# xkid_sensor_0_1.net
KiCad netlist of a schematic drawn in EAGLE
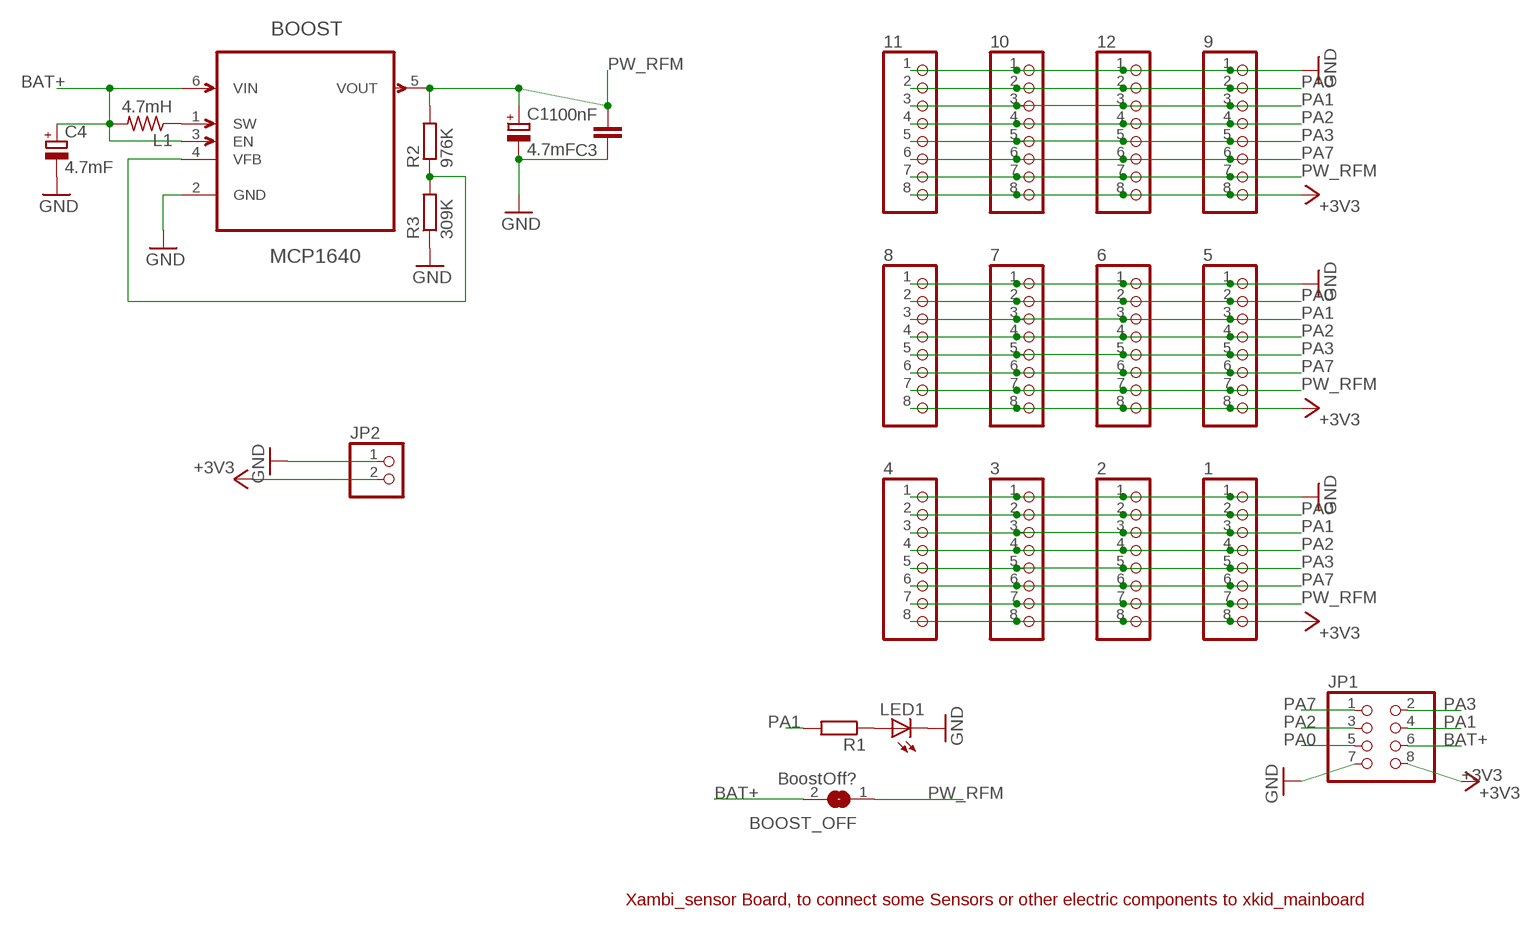
[diagram p0: schematic, sheet 1]

(export (version "E")
  (design (tool "Eeschema 10.0.6"))
  (components
    (comp (ref "1")
      (value "PINHD-1X8_2.00")
      (footprint "eagle-import:1X08M")
      (libsource (lib "eagle-import") (part "PINHD-1X8_2.00"))
    )
    (comp (ref "2")
      (value "PINHD-1X8_2.00")
      (footprint "eagle-import:1X08M")
      (libsource (lib "eagle-import") (part "PINHD-1X8_2.00"))
    )
    (comp (ref "3")
      (value "PINHD-1X8_2.00")
      (footprint "eagle-import:1X08M")
      (libsource (lib "eagle-import") (part "PINHD-1X8_2.00"))
    )
    (comp (ref "4")
      (value "PINHD-1X8_2.00")
      (footprint "eagle-import:1X08M")
      (libsource (lib "eagle-import") (part "PINHD-1X8_2.00"))
    )
    (comp (ref "5")
      (value "PINHD-1X8_2.00")
      (footprint "eagle-import:1X08M")
      (libsource (lib "eagle-import") (part "PINHD-1X8_2.00"))
    )
    (comp (ref "6")
      (value "PINHD-1X8_2.00")
      (footprint "eagle-import:1X08M")
      (libsource (lib "eagle-import") (part "PINHD-1X8_2.00"))
    )
    (comp (ref "7")
      (value "PINHD-1X8_2.00")
      (footprint "eagle-import:1X08M")
      (libsource (lib "eagle-import") (part "PINHD-1X8_2.00"))
    )
    (comp (ref "8")
      (value "PINHD-1X8_2.00")
      (footprint "eagle-import:1X08M")
      (libsource (lib "eagle-import") (part "PINHD-1X8_2.00"))
    )
    (comp (ref "9")
      (value "PINHD-1X8_2.00")
      (footprint "eagle-import:1X08M")
      (libsource (lib "eagle-import") (part "PINHD-1X8_2.00"))
    )
    (comp (ref "10")
      (value "PINHD-1X8_2.00")
      (footprint "eagle-import:1X08M")
      (libsource (lib "eagle-import") (part "PINHD-1X8_2.00"))
    )
    (comp (ref "11")
      (value "PINHD-1X8_2.00")
      (footprint "eagle-import:1X08M")
      (libsource (lib "eagle-import") (part "PINHD-1X8_2.00"))
    )
    (comp (ref "12")
      (value "PINHD-1X8_2.00")
      (footprint "eagle-import:1X08M")
      (libsource (lib "eagle-import") (part "PINHD-1X8_2.00"))
    )
    (comp (ref "BOOST")
      (value "MCP1640")
      (footprint "eagle-import:SOT95P270X145-6N")
      (fields (field (name "MPN") "MCP1640BT-I/CHY"))
      (libsource (lib "eagle-import") (part "MCP1640BT-I/CHY"))
    )
    (comp (ref "BOOST_OFF")
      (value "BoostOff?")
      (footprint "eagle-import:SJ")
      (libsource (lib "eagle-import") (part "SJ"))
    )
    (comp (ref "C1")
      (value "4.7mF")
      (footprint "eagle-import:CT3216")
      (libsource (lib "eagle-import") (part "CPOL-EUCT3216"))
    )
    (comp (ref "C3")
      (value "100nF")
      (footprint "eagle-import:C0805K")
      (libsource (lib "eagle-import") (part "C-EUC0805K"))
    )
    (comp (ref "C4")
      (value "4.7mF")
      (footprint "eagle-import:CT3216")
      (libsource (lib "eagle-import") (part "CPOL-EUCT3216"))
    )
    (comp (ref "JP1")
      (value "PINHD-2X4_2.54")
      (footprint "eagle-import:2X04")
      (libsource (lib "eagle-import") (part "PINHD-2X4_2.54"))
    )
    (comp (ref "JP2")
      (value "PINHD-1X2")
      (footprint "eagle-import:1X02")
      (libsource (lib "eagle-import") (part "PINHD-1X2"))
    )
    (comp (ref "L1")
      (value "4.7mH")
      (footprint "eagle-import:0204_5")
      (libsource (lib "eagle-import") (part "R-US_0204/5"))
    )
    (comp (ref "LED1")
      (value "LEDCHIPLED_0805")
      (footprint "eagle-import:CHIPLED_0805")
      (libsource (lib "eagle-import") (part "LEDCHIPLED_0805"))
    )
    (comp (ref "R1")
      (value "R-EU_R0805")
      (footprint "eagle-import:R0805")
      (libsource (lib "eagle-import") (part "R-EU_R0805"))
    )
    (comp (ref "R2")
      (value "976K")
      (footprint "eagle-import:R0805")
      (libsource (lib "eagle-import") (part "R-EU_R0805"))
    )
    (comp (ref "R3")
      (value "309K")
      (footprint "eagle-import:R0805")
      (libsource (lib "eagle-import") (part "R-EU_R0805"))
    )
  )
  (nets
    (net (code "1") (name "+3V3") (class "Default")
      (node (ref "1") (pin "8") (pinfunction "8_8") (pintype "passive"))
      (node (ref "10") (pin "8") (pinfunction "8_8") (pintype "passive"))
      (node (ref "11") (pin "8") (pinfunction "8_8") (pintype "passive"))
      (node (ref "12") (pin "8") (pinfunction "8_8") (pintype "passive"))
      (node (ref "2") (pin "8") (pinfunction "8_8") (pintype "passive"))
      (node (ref "3") (pin "8") (pinfunction "8_8") (pintype "passive"))
      (node (ref "4") (pin "8") (pinfunction "8_8") (pintype "passive"))
      (node (ref "5") (pin "8") (pinfunction "8_8") (pintype "passive"))
      (node (ref "6") (pin "8") (pinfunction "8_8") (pintype "passive"))
      (node (ref "7") (pin "8") (pinfunction "8_8") (pintype "passive"))
      (node (ref "8") (pin "8") (pinfunction "8_8") (pintype "passive"))
      (node (ref "9") (pin "8") (pinfunction "8_8") (pintype "passive"))
      (node (ref "JP1") (pin "8") (pinfunction "8_8") (pintype "passive"))
      (node (ref "JP2") (pin "2") (pinfunction "2_2") (pintype "passive"))
    )
    (net (code "2") (name "/BAT+") (class "Default")
      (node (ref "BOOST") (pin "3") (pinfunction "EN_3") (pintype "input"))
      (node (ref "BOOST") (pin "6") (pinfunction "VIN_6") (pintype "input"))
      (node (ref "BOOST_OFF") (pin "2") (pinfunction "2_2") (pintype "passive"))
      (node (ref "C4") (pin "+") (pinfunction "+_+") (pintype "passive"))
      (node (ref "JP1") (pin "6") (pinfunction "6_6") (pintype "passive"))
      (node (ref "L1") (pin "2") (pinfunction "2_2") (pintype "passive"))
    )
    (net (code "3") (name "/PA0") (class "Default")
      (node (ref "1") (pin "2") (pinfunction "2_2") (pintype "passive"))
      (node (ref "10") (pin "2") (pinfunction "2_2") (pintype "passive"))
      (node (ref "11") (pin "2") (pinfunction "2_2") (pintype "passive"))
      (node (ref "12") (pin "2") (pinfunction "2_2") (pintype "passive"))
      (node (ref "2") (pin "2") (pinfunction "2_2") (pintype "passive"))
      (node (ref "3") (pin "2") (pinfunction "2_2") (pintype "passive"))
      (node (ref "4") (pin "2") (pinfunction "2_2") (pintype "passive"))
      (node (ref "5") (pin "2") (pinfunction "2_2") (pintype "passive"))
      (node (ref "6") (pin "2") (pinfunction "2_2") (pintype "passive"))
      (node (ref "7") (pin "2") (pinfunction "2_2") (pintype "passive"))
      (node (ref "8") (pin "2") (pinfunction "2_2") (pintype "passive"))
      (node (ref "9") (pin "2") (pinfunction "2_2") (pintype "passive"))
      (node (ref "JP1") (pin "5") (pinfunction "5_5") (pintype "passive"))
    )
    (net (code "4") (name "/PA1") (class "Default")
      (node (ref "1") (pin "3") (pinfunction "3_3") (pintype "passive"))
      (node (ref "10") (pin "3") (pinfunction "3_3") (pintype "passive"))
      (node (ref "11") (pin "3") (pinfunction "3_3") (pintype "passive"))
      (node (ref "12") (pin "3") (pinfunction "3_3") (pintype "passive"))
      (node (ref "2") (pin "3") (pinfunction "3_3") (pintype "passive"))
      (node (ref "3") (pin "3") (pinfunction "3_3") (pintype "passive"))
      (node (ref "4") (pin "3") (pinfunction "3_3") (pintype "passive"))
      (node (ref "5") (pin "3") (pinfunction "3_3") (pintype "passive"))
      (node (ref "6") (pin "3") (pinfunction "3_3") (pintype "passive"))
      (node (ref "7") (pin "3") (pinfunction "3_3") (pintype "passive"))
      (node (ref "8") (pin "3") (pinfunction "3_3") (pintype "passive"))
      (node (ref "9") (pin "3") (pinfunction "3_3") (pintype "passive"))
      (node (ref "JP1") (pin "4") (pinfunction "4_4") (pintype "passive"))
      (node (ref "R1") (pin "2") (pinfunction "2_2") (pintype "passive"))
    )
    (net (code "5") (name "/PA2") (class "Default")
      (node (ref "1") (pin "4") (pinfunction "4_4") (pintype "passive"))
      (node (ref "10") (pin "4") (pinfunction "4_4") (pintype "passive"))
      (node (ref "11") (pin "4") (pinfunction "4_4") (pintype "passive"))
      (node (ref "12") (pin "4") (pinfunction "4_4") (pintype "passive"))
      (node (ref "2") (pin "4") (pinfunction "4_4") (pintype "passive"))
      (node (ref "3") (pin "4") (pinfunction "4_4") (pintype "passive"))
      (node (ref "4") (pin "4") (pinfunction "4_4") (pintype "passive"))
      (node (ref "5") (pin "4") (pinfunction "4_4") (pintype "passive"))
      (node (ref "6") (pin "4") (pinfunction "4_4") (pintype "passive"))
      (node (ref "7") (pin "4") (pinfunction "4_4") (pintype "passive"))
      (node (ref "8") (pin "4") (pinfunction "4_4") (pintype "passive"))
      (node (ref "9") (pin "4") (pinfunction "4_4") (pintype "passive"))
      (node (ref "JP1") (pin "3") (pinfunction "3_3") (pintype "passive"))
    )
    (net (code "6") (name "/PA3") (class "Default")
      (node (ref "1") (pin "5") (pinfunction "5_5") (pintype "passive"))
      (node (ref "10") (pin "5") (pinfunction "5_5") (pintype "passive"))
      (node (ref "11") (pin "5") (pinfunction "5_5") (pintype "passive"))
      (node (ref "12") (pin "5") (pinfunction "5_5") (pintype "passive"))
      (node (ref "2") (pin "5") (pinfunction "5_5") (pintype "passive"))
      (node (ref "3") (pin "5") (pinfunction "5_5") (pintype "passive"))
      (node (ref "4") (pin "5") (pinfunction "5_5") (pintype "passive"))
      (node (ref "5") (pin "5") (pinfunction "5_5") (pintype "passive"))
      (node (ref "6") (pin "5") (pinfunction "5_5") (pintype "passive"))
      (node (ref "7") (pin "5") (pinfunction "5_5") (pintype "passive"))
      (node (ref "8") (pin "5") (pinfunction "5_5") (pintype "passive"))
      (node (ref "9") (pin "5") (pinfunction "5_5") (pintype "passive"))
      (node (ref "JP1") (pin "2") (pinfunction "2_2") (pintype "passive"))
    )
    (net (code "7") (name "/PA7") (class "Default")
      (node (ref "1") (pin "6") (pinfunction "6_6") (pintype "passive"))
      (node (ref "10") (pin "6") (pinfunction "6_6") (pintype "passive"))
      (node (ref "11") (pin "6") (pinfunction "6_6") (pintype "passive"))
      (node (ref "12") (pin "6") (pinfunction "6_6") (pintype "passive"))
      (node (ref "2") (pin "6") (pinfunction "6_6") (pintype "passive"))
      (node (ref "3") (pin "6") (pinfunction "6_6") (pintype "passive"))
      (node (ref "4") (pin "6") (pinfunction "6_6") (pintype "passive"))
      (node (ref "5") (pin "6") (pinfunction "6_6") (pintype "passive"))
      (node (ref "6") (pin "6") (pinfunction "6_6") (pintype "passive"))
      (node (ref "7") (pin "6") (pinfunction "6_6") (pintype "passive"))
      (node (ref "8") (pin "6") (pinfunction "6_6") (pintype "passive"))
      (node (ref "9") (pin "6") (pinfunction "6_6") (pintype "passive"))
      (node (ref "JP1") (pin "1") (pinfunction "1_1") (pintype "passive"))
    )
    (net (code "8") (name "/PW_RFM") (class "Default")
      (node (ref "1") (pin "7") (pinfunction "7_7") (pintype "passive"))
      (node (ref "10") (pin "7") (pinfunction "7_7") (pintype "passive"))
      (node (ref "11") (pin "7") (pinfunction "7_7") (pintype "passive"))
      (node (ref "12") (pin "7") (pinfunction "7_7") (pintype "passive"))
      (node (ref "2") (pin "7") (pinfunction "7_7") (pintype "passive"))
      (node (ref "3") (pin "7") (pinfunction "7_7") (pintype "passive"))
      (node (ref "4") (pin "7") (pinfunction "7_7") (pintype "passive"))
      (node (ref "5") (pin "7") (pinfunction "7_7") (pintype "passive"))
      (node (ref "6") (pin "7") (pinfunction "7_7") (pintype "passive"))
      (node (ref "7") (pin "7") (pinfunction "7_7") (pintype "passive"))
      (node (ref "8") (pin "7") (pinfunction "7_7") (pintype "passive"))
      (node (ref "9") (pin "7") (pinfunction "7_7") (pintype "passive"))
      (node (ref "BOOST") (pin "5") (pinfunction "VOUT_5") (pintype "output"))
      (node (ref "BOOST_OFF") (pin "1") (pinfunction "1_1") (pintype "passive"))
      (node (ref "C1") (pin "+") (pinfunction "+_+") (pintype "passive"))
      (node (ref "C3") (pin "2") (pinfunction "2_2") (pintype "passive"))
      (node (ref "R2") (pin "2") (pinfunction "2_2") (pintype "passive"))
    )
    (net (code "9") (name "GND") (class "Default")
      (node (ref "1") (pin "1") (pinfunction "1_1") (pintype "passive"))
      (node (ref "10") (pin "1") (pinfunction "1_1") (pintype "passive"))
      (node (ref "11") (pin "1") (pinfunction "1_1") (pintype "passive"))
      (node (ref "12") (pin "1") (pinfunction "1_1") (pintype "passive"))
      (node (ref "2") (pin "1") (pinfunction "1_1") (pintype "passive"))
      (node (ref "3") (pin "1") (pinfunction "1_1") (pintype "passive"))
      (node (ref "4") (pin "1") (pinfunction "1_1") (pintype "passive"))
      (node (ref "5") (pin "1") (pinfunction "1_1") (pintype "passive"))
      (node (ref "6") (pin "1") (pinfunction "1_1") (pintype "passive"))
      (node (ref "7") (pin "1") (pinfunction "1_1") (pintype "passive"))
      (node (ref "8") (pin "1") (pinfunction "1_1") (pintype "passive"))
      (node (ref "9") (pin "1") (pinfunction "1_1") (pintype "passive"))
      (node (ref "BOOST") (pin "2") (pinfunction "GND_2") (pintype "passive"))
      (node (ref "C1") (pin "-") (pinfunction "-_-") (pintype "passive"))
      (node (ref "C3") (pin "1") (pinfunction "1_1") (pintype "passive"))
      (node (ref "C4") (pin "-") (pinfunction "-_-") (pintype "passive"))
      (node (ref "JP1") (pin "7") (pinfunction "7_7") (pintype "passive"))
      (node (ref "JP2") (pin "1") (pinfunction "1_1") (pintype "passive"))
      (node (ref "LED1") (pin "C") (pinfunction "C_C") (pintype "passive"))
      (node (ref "R3") (pin "1") (pinfunction "1_1") (pintype "passive"))
    )
    (net (code "10") (name "Net-(BOOST-SW)") (class "Default")
      (node (ref "BOOST") (pin "1") (pinfunction "SW_1") (pintype "input"))
      (node (ref "L1") (pin "1") (pinfunction "1_1") (pintype "passive"))
    )
    (net (code "11") (name "Net-(BOOST-VFB)") (class "Default")
      (node (ref "BOOST") (pin "4") (pinfunction "VFB_4") (pintype "input"))
      (node (ref "R2") (pin "1") (pinfunction "1_1") (pintype "passive"))
      (node (ref "R3") (pin "2") (pinfunction "2_2") (pintype "passive"))
    )
    (net (code "12") (name "Net-(LED1-PadA)") (class "Default")
      (node (ref "LED1") (pin "A") (pinfunction "A_A") (pintype "passive"))
      (node (ref "R1") (pin "1") (pinfunction "1_1") (pintype "passive"))
    )
  )
)
